# amc6821-breakout-v2_0.net
KiCad netlist of a schematic drawn in EAGLE
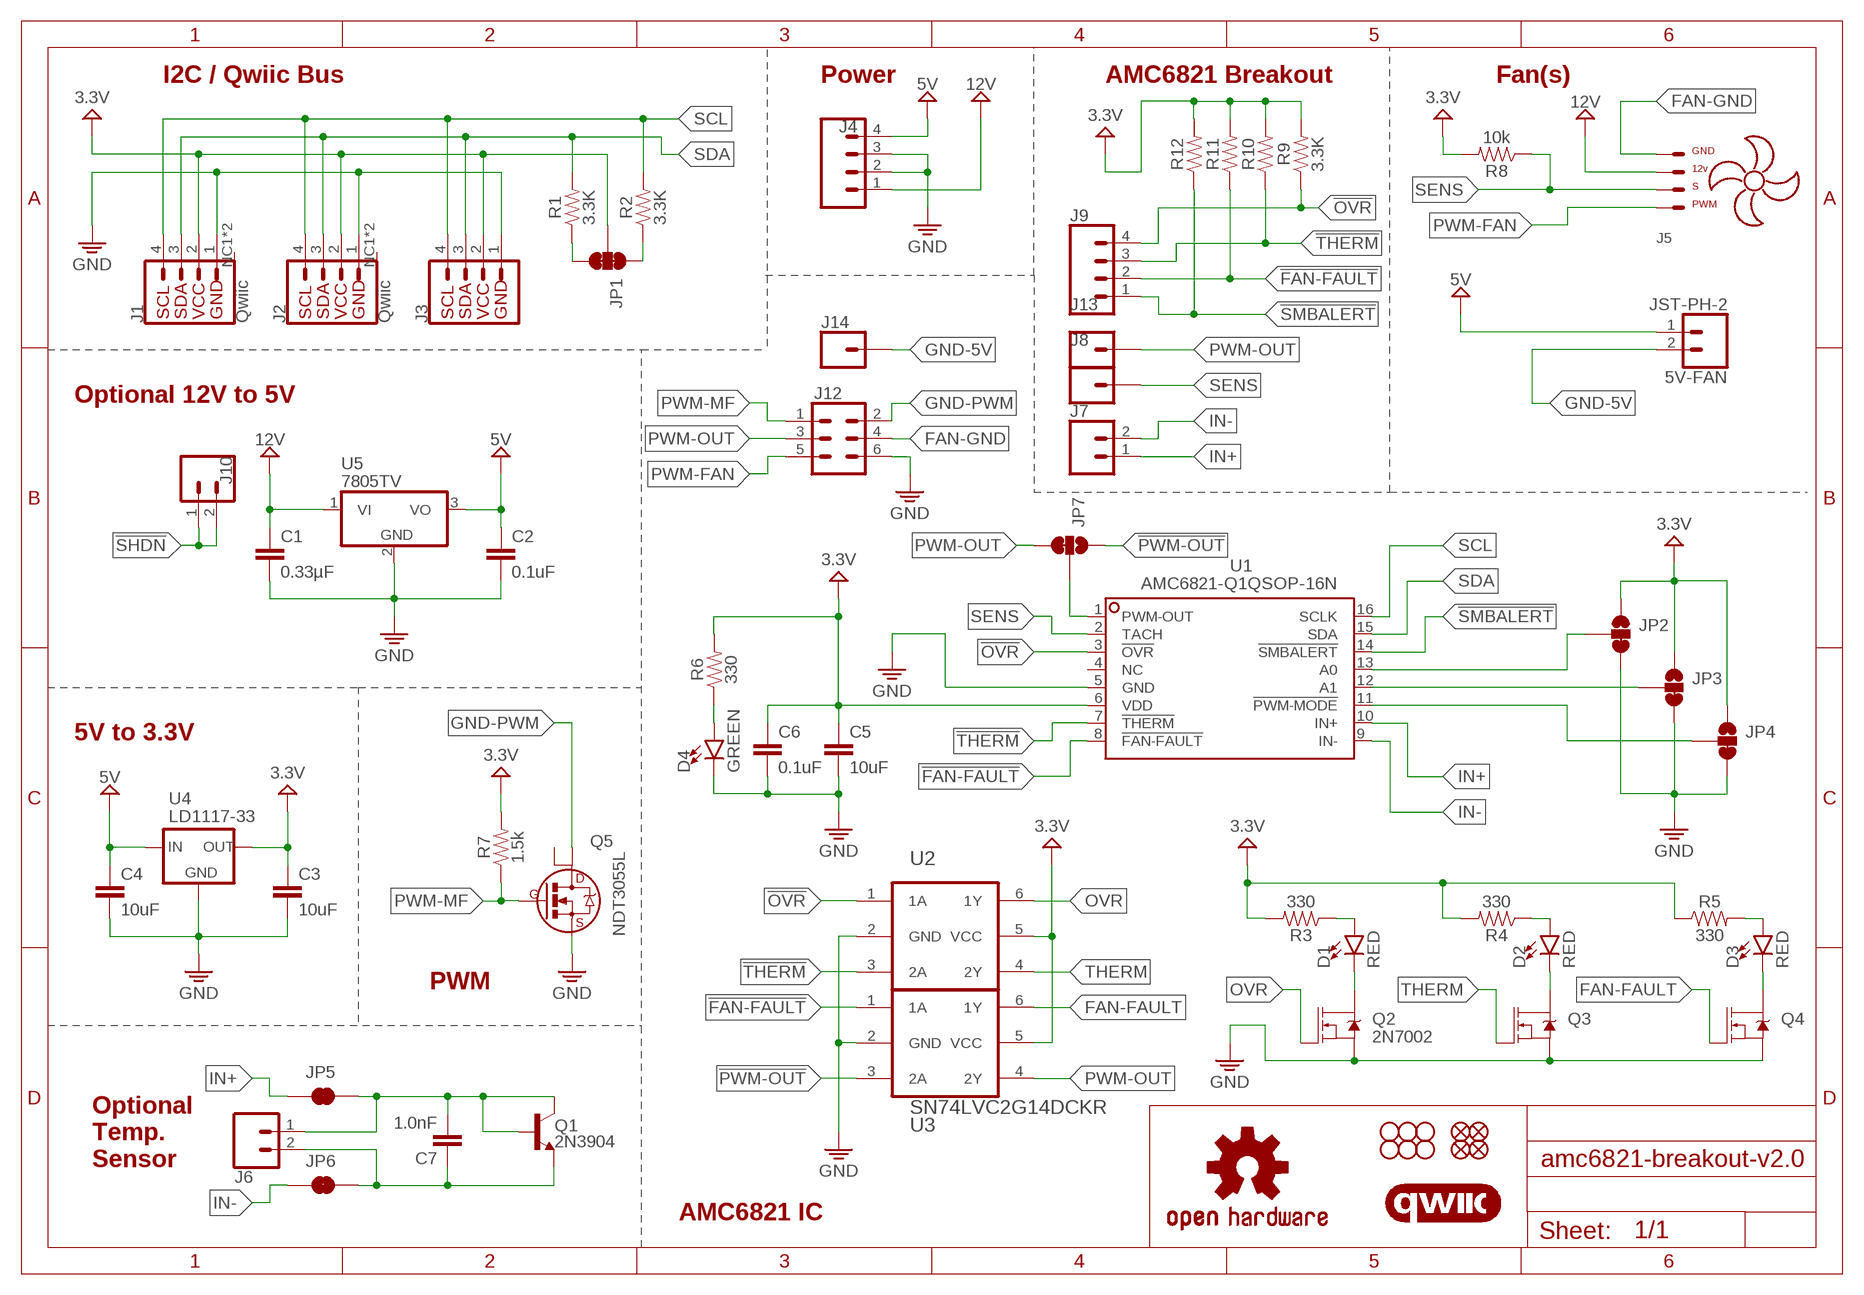
[diagram p0: schematic, sheet 1]

(export (version "E")
  (design (tool "Eeschema 10.0.6"))
  (components
    (comp (ref "5V-FAN")
      (value "JST-PH-2")
      (footprint "eagle-import:JST-PH2")
      (libsource (lib "eagle-import") (part "JST-PH-2"))
    )
    (comp (ref "C1")
      (value "0.33µF")
      (footprint "eagle-import:0805")
      (libsource (lib "eagle-import") (part "0.33UF/330NF-0805-50V-10%"))
    )
    (comp (ref "C2")
      (value "0.1uF")
      (footprint "eagle-import:0603")
      (libsource (lib "eagle-import") (part "0.1UF-0603-25V-5%"))
    )
    (comp (ref "C3")
      (value "10uF")
      (footprint "eagle-import:0603")
      (libsource (lib "eagle-import") (part "10UF-0603-6.3V-20%"))
    )
    (comp (ref "C4")
      (value "10uF")
      (footprint "eagle-import:0603")
      (libsource (lib "eagle-import") (part "10UF-0603-6.3V-20%"))
    )
    (comp (ref "C5")
      (value "10uF")
      (footprint "eagle-import:0603")
      (libsource (lib "eagle-import") (part "10UF-0603-6.3V-20%"))
    )
    (comp (ref "C6")
      (value "0.1uF")
      (footprint "eagle-import:0603")
      (libsource (lib "eagle-import") (part "0.1UF-0603-25V-5%"))
    )
    (comp (ref "C7")
      (value "1.0nF")
      (footprint "eagle-import:0402-TIGHT")
      (libsource (lib "eagle-import") (part "1.0NF/1000PF-0402_TIGHT-50V-10%"))
    )
    (comp (ref "D1")
      (value "RED")
      (footprint "eagle-import:LED-0603")
      (libsource (lib "eagle-import") (part "LED-RED0603"))
    )
    (comp (ref "D2")
      (value "RED")
      (footprint "eagle-import:LED-0603")
      (libsource (lib "eagle-import") (part "LED-RED0603"))
    )
    (comp (ref "D3")
      (value "RED")
      (footprint "eagle-import:LED-0603")
      (libsource (lib "eagle-import") (part "LED-RED0603"))
    )
    (comp (ref "D4")
      (value "GREEN")
      (footprint "eagle-import:LED-0603")
      (libsource (lib "eagle-import") (part "LED-GREEN0603"))
    )
    (comp (ref "FD1")
      (value "FIDUCIALUFIDUCIAL")
      (footprint "eagle-import:FIDUCIAL-MICRO")
      (libsource (lib "eagle-import") (part "FIDUCIALUFIDUCIAL"))
    )
    (comp (ref "FD2")
      (value "FIDUCIALUFIDUCIAL")
      (footprint "eagle-import:FIDUCIAL-MICRO")
      (libsource (lib "eagle-import") (part "FIDUCIALUFIDUCIAL"))
    )
    (comp (ref "FD3")
      (value "FIDUCIALUFIDUCIAL")
      (footprint "eagle-import:FIDUCIAL-MICRO")
      (libsource (lib "eagle-import") (part "FIDUCIALUFIDUCIAL"))
    )
    (comp (ref "FD4")
      (value "FIDUCIALUFIDUCIAL")
      (footprint "eagle-import:FIDUCIAL-MICRO")
      (libsource (lib "eagle-import") (part "FIDUCIALUFIDUCIAL"))
    )
    (comp (ref "H1")
      (value "STAND-OFF")
      (footprint "eagle-import:STAND-OFF")
      (libsource (lib "eagle-import") (part "STAND-OFF"))
    )
    (comp (ref "H2")
      (value "STAND-OFF")
      (footprint "eagle-import:STAND-OFF")
      (libsource (lib "eagle-import") (part "STAND-OFF"))
    )
    (comp (ref "H3")
      (value "STAND-OFF")
      (footprint "eagle-import:STAND-OFF")
      (libsource (lib "eagle-import") (part "STAND-OFF"))
    )
    (comp (ref "H4")
      (value "STAND-OFF")
      (footprint "eagle-import:STAND-OFF")
      (libsource (lib "eagle-import") (part "STAND-OFF"))
    )
    (comp (ref "H5")
      (value "STAND-OFF")
      (footprint "eagle-import:STAND-OFF")
      (libsource (lib "eagle-import") (part "STAND-OFF"))
    )
    (comp (ref "H6")
      (value "STAND-OFF")
      (footprint "eagle-import:STAND-OFF")
      (libsource (lib "eagle-import") (part "STAND-OFF"))
    )
    (comp (ref "J1")
      (value "Qwiic")
      (footprint "eagle-import:JST04_1MM_VERT")
      (libsource (lib "eagle-import") (part "QWIIC_CONNECTOR"))
    )
    (comp (ref "J2")
      (value "Qwiic")
      (footprint "eagle-import:JST04_1MM_VERT")
      (libsource (lib "eagle-import") (part "QWIIC_CONNECTOR"))
    )
    (comp (ref "J3")
      (value "I2C_STANDARD")
      (footprint "eagle-import:1X04")
      (libsource (lib "eagle-import") (part "I2C_STANDARD"))
    )
    (comp (ref "J4")
      (value "CONN_04SCREW")
      (footprint "eagle-import:SCREWTERMINAL-3.5MM-4")
      (libsource (lib "eagle-import") (part "CONN_04SCREW"))
    )
    (comp (ref "J5")
      (value "KK-254-4KK-254")
      (footprint "eagle-import:MOLEX_47053-1000")
      (libsource (lib "eagle-import") (part "KK-254-4KK-254"))
    )
    (comp (ref "J6")
      (value "CONN_02")
      (footprint "eagle-import:1X02")
      (libsource (lib "eagle-import") (part "CONN_02"))
    )
    (comp (ref "J7")
      (value "CONN_02")
      (footprint "eagle-import:1X02")
      (libsource (lib "eagle-import") (part "CONN_02"))
    )
    (comp (ref "J8")
      (value "CONN_01")
      (footprint "eagle-import:1X01")
      (libsource (lib "eagle-import") (part "CONN_01"))
    )
    (comp (ref "J9")
      (value "CONN_04PTH")
      (footprint "eagle-import:1X04")
      (libsource (lib "eagle-import") (part "CONN_04PTH"))
    )
    (comp (ref "J10")
      (value "CONN_021X02_NO_SILK")
      (footprint "eagle-import:1X02_NO_SILK")
      (libsource (lib "eagle-import") (part "CONN_021X02_NO_SILK"))
    )
    (comp (ref "J12")
      (value "CONN_03X2NO_SILK")
      (footprint "eagle-import:2X3-NS")
      (libsource (lib "eagle-import") (part "CONN_03X2NO_SILK"))
    )
    (comp (ref "J13")
      (value "CONN_01")
      (footprint "eagle-import:1X01")
      (libsource (lib "eagle-import") (part "CONN_01"))
    )
    (comp (ref "J14")
      (value "CONN_01")
      (footprint "eagle-import:1X01")
      (libsource (lib "eagle-import") (part "CONN_01"))
    )
    (comp (ref "JP1")
      (value "JUMPER-SMT_3_2-NC_TRACE_SILK")
      (footprint "eagle-import:SMT-JUMPER_3_2-NC_TRACE_SILK")
      (libsource (lib "eagle-import") (part "JUMPER-SMT_3_2-NC_TRACE_SILK"))
    )
    (comp (ref "JP2")
      (value "JUMPER-SMT_3_1-NC_TRACE_SILK")
      (footprint "eagle-import:SMT-JUMPER_3_1-NC_TRACE_SILK")
      (libsource (lib "eagle-import") (part "JUMPER-SMT_3_1-NC_TRACE_SILK"))
    )
    (comp (ref "JP3")
      (value "JUMPER-SMT_3_1-NC_TRACE_SILK")
      (footprint "eagle-import:SMT-JUMPER_3_1-NC_TRACE_SILK")
      (libsource (lib "eagle-import") (part "JUMPER-SMT_3_1-NC_TRACE_SILK"))
    )
    (comp (ref "JP4")
      (value "JUMPER-SMT_3_1-NC_TRACE_SILK")
      (footprint "eagle-import:SMT-JUMPER_3_1-NC_TRACE_SILK")
      (libsource (lib "eagle-import") (part "JUMPER-SMT_3_1-NC_TRACE_SILK"))
    )
    (comp (ref "JP5")
      (value "JUMPER-SMT_2_NC_TRACE_SILK")
      (footprint "eagle-import:SMT-JUMPER_2_NC_TRACE_SILK")
      (libsource (lib "eagle-import") (part "JUMPER-SMT_2_NC_TRACE_SILK"))
    )
    (comp (ref "JP6")
      (value "JUMPER-SMT_2_NC_TRACE_SILK")
      (footprint "eagle-import:SMT-JUMPER_2_NC_TRACE_SILK")
      (libsource (lib "eagle-import") (part "JUMPER-SMT_2_NC_TRACE_SILK"))
    )
    (comp (ref "JP7")
      (value "JUMPER-SMT_3_1-NC_TRACE_SILK")
      (footprint "eagle-import:SMT-JUMPER_3_1-NC_TRACE_SILK")
      (libsource (lib "eagle-import") (part "JUMPER-SMT_3_1-NC_TRACE_SILK"))
    )
    (comp (ref "LOGO1")
      (value "OSHW-LOGOS")
      (footprint "eagle-import:OSHW-LOGO-S")
      (libsource (lib "eagle-import") (part "OSHW-LOGOS"))
    )
    (comp (ref "LOGO2")
      (value "QWIIC_LOGO_6MM")
      (footprint "eagle-import:QWIIC_6MM")
      (libsource (lib "eagle-import") (part "QWIIC_LOGO_6MM"))
    )
    (comp (ref "Q1")
      (value "2N3904")
      (footprint "eagle-import:SOT23-3")
      (libsource (lib "eagle-import") (part "TRANS_NPN-MMBTA42"))
    )
    (comp (ref "Q2")
      (value "2N7002")
      (footprint "eagle-import:SOT323")
      (libsource (lib "eagle-import") (part "MOSFET-NCH-2N7002PW"))
    )
    (comp (ref "Q3")
      (value "310mA/60V/1.6Ω")
      (footprint "eagle-import:SOT323")
      (libsource (lib "eagle-import") (part "MOSFET-NCH-2N7002PW"))
    )
    (comp (ref "Q4")
      (value "310mA/60V/1.6Ω")
      (footprint "eagle-import:SOT323")
      (libsource (lib "eagle-import") (part "MOSFET-NCH-2N7002PW"))
    )
    (comp (ref "Q5")
      (value "NDT3055L")
      (footprint "eagle-import:SOT223")
      (libsource (lib "eagle-import") (part "NDT3055L"))
    )
    (comp (ref "R1")
      (value "3.3K")
      (footprint "eagle-import:0805")
      (libsource (lib "eagle-import") (part "RESISTOR0805"))
    )
    (comp (ref "R2")
      (value "3.3K")
      (footprint "eagle-import:0805")
      (libsource (lib "eagle-import") (part "RESISTOR0805"))
    )
    (comp (ref "R3")
      (value "330")
      (footprint "eagle-import:0805")
      (libsource (lib "eagle-import") (part "RESISTOR0805"))
    )
    (comp (ref "R4")
      (value "330")
      (footprint "eagle-import:0805")
      (libsource (lib "eagle-import") (part "RESISTOR0805"))
    )
    (comp (ref "R5")
      (value "330")
      (footprint "eagle-import:0805")
      (libsource (lib "eagle-import") (part "RESISTOR0805"))
    )
    (comp (ref "R6")
      (value "330")
      (footprint "eagle-import:0805")
      (libsource (lib "eagle-import") (part "RESISTOR0805"))
    )
    (comp (ref "R7")
      (value "1.5k")
      (footprint "eagle-import:0603")
      (libsource (lib "eagle-import") (part "1.5KOHM-0603-1/10W-1%"))
    )
    (comp (ref "R8")
      (value "10k")
      (footprint "eagle-import:0603")
      (libsource (lib "eagle-import") (part "10KOHM-0603-1/10W-1%"))
    )
    (comp (ref "R9")
      (value "3.3K")
      (footprint "eagle-import:0805")
      (libsource (lib "eagle-import") (part "RESISTOR0805"))
    )
    (comp (ref "R10")
      (value "3.3K")
      (footprint "eagle-import:0805")
      (libsource (lib "eagle-import") (part "RESISTOR0805"))
    )
    (comp (ref "R11")
      (value "3.3K")
      (footprint "eagle-import:0805")
      (libsource (lib "eagle-import") (part "RESISTOR0805"))
    )
    (comp (ref "R12")
      (value "3.3K")
      (footprint "eagle-import:0805")
      (libsource (lib "eagle-import") (part "RESISTOR0805"))
    )
    (comp (ref "U1")
      (value "AMC6821-Q1QSOP-16N")
      (footprint "eagle-import:QSOP-16N")
      (libsource (lib "eagle-import") (part "AMC6821-Q1QSOP-16N"))
    )
    (comp (ref "U2")
      (value "SN74LVC2G14DCKR")
      (footprint "eagle-import:SOT65P210X110-6N")
      (libsource (lib "eagle-import") (part "SN74LVC2G14DCKR"))
    )
    (comp (ref "U3")
      (value "SN74LVC2G14DCKR")
      (footprint "eagle-import:SOT65P210X110-6N")
      (libsource (lib "eagle-import") (part "SN74LVC2G14DCKR"))
    )
    (comp (ref "U4")
      (value "LD1117-33")
      (footprint "eagle-import:SOT223")
      (libsource (lib "eagle-import") (part "V_REG_LD1117VXXLD1117-SMD"))
    )
    (comp (ref "U5")
      (value "7805TV")
      (footprint "eagle-import:TO220V")
      (libsource (lib "eagle-import") (part "78TV05"))
    )
  )
  (nets
    (net (code "1") (name "/~{FAN-FAULT}") (class "Default")
      (node (ref "J9") (pin "2") (pinfunction "2_2") (pintype "passive"))
      (node (ref "R11") (pin "1") (pinfunction "1_1") (pintype "passive"))
      (node (ref "U1") (pin "8") (pinfunction "~{FAN-FAULT}_8") (pintype "output"))
      (node (ref "U3") (pin "1") (pinfunction "1A_1") (pintype "input"))
    )
    (net (code "2") (name "/~{OVR}") (class "Default")
      (node (ref "J9") (pin "4") (pinfunction "4_4") (pintype "passive"))
      (node (ref "R9") (pin "1") (pinfunction "1_1") (pintype "passive"))
      (node (ref "U1") (pin "3") (pinfunction "~{OVR}_3") (pintype "output"))
      (node (ref "U2") (pin "1") (pinfunction "1A_1") (pintype "input"))
    )
    (net (code "3") (name "/~{PWM-OUT}") (class "Default")
      (node (ref "JP7") (pin "1") (pinfunction "1_1") (pintype "passive"))
      (node (ref "U3") (pin "3") (pinfunction "2A_3") (pintype "input"))
    )
    (net (code "4") (name "/~{SHDN}") (class "Default")
      (node (ref "J10") (pin "1") (pinfunction "1_1") (pintype "passive"))
      (node (ref "J10") (pin "2") (pinfunction "2_2") (pintype "passive"))
    )
    (net (code "5") (name "/~{SMBALERT}") (class "Default")
      (node (ref "J9") (pin "1") (pinfunction "1_1") (pintype "passive"))
      (node (ref "R12") (pin "1") (pinfunction "1_1") (pintype "passive"))
      (node (ref "U1") (pin "14") (pinfunction "~{SMBALERT}_14") (pintype "input"))
    )
    (net (code "6") (name "/~{THERM}") (class "Default")
      (node (ref "J9") (pin "3") (pinfunction "3_3") (pintype "passive"))
      (node (ref "R10") (pin "1") (pinfunction "1_1") (pintype "passive"))
      (node (ref "U1") (pin "7") (pinfunction "~{THERM}_7") (pintype "bidirectional"))
      (node (ref "U2") (pin "3") (pinfunction "2A_3") (pintype "input"))
    )
    (net (code "7") (name "3.3V") (class "Default")
      (node (ref "C3") (pin "1") (pinfunction "1_1") (pintype "passive"))
      (node (ref "C5") (pin "1") (pinfunction "1_1") (pintype "passive"))
      (node (ref "C6") (pin "1") (pinfunction "1_1") (pintype "passive"))
      (node (ref "J1") (pin "2") (pinfunction "2_2") (pintype "power_in"))
      (node (ref "J2") (pin "2") (pinfunction "2_2") (pintype "power_in"))
      (node (ref "J3") (pin "2") (pinfunction "2_2") (pintype "power_in"))
      (node (ref "JP1") (pin "2") (pinfunction "2_2") (pintype "passive"))
      (node (ref "JP2") (pin "1") (pinfunction "1_1") (pintype "passive"))
      (node (ref "JP3") (pin "1") (pinfunction "1_1") (pintype "passive"))
      (node (ref "JP4") (pin "1") (pinfunction "1_1") (pintype "passive"))
      (node (ref "R10") (pin "2") (pinfunction "2_2") (pintype "passive"))
      (node (ref "R11") (pin "2") (pinfunction "2_2") (pintype "passive"))
      (node (ref "R12") (pin "2") (pinfunction "2_2") (pintype "passive"))
      (node (ref "R3") (pin "2") (pinfunction "2_2") (pintype "passive"))
      (node (ref "R4") (pin "2") (pinfunction "2_2") (pintype "passive"))
      (node (ref "R5") (pin "1") (pinfunction "1_1") (pintype "passive"))
      (node (ref "R6") (pin "2") (pinfunction "2_2") (pintype "passive"))
      (node (ref "R7") (pin "2") (pinfunction "2_2") (pintype "passive"))
      (node (ref "R8") (pin "2") (pinfunction "2_2") (pintype "passive"))
      (node (ref "R9") (pin "2") (pinfunction "2_2") (pintype "passive"))
      (node (ref "U1") (pin "6") (pinfunction "VDD_6") (pintype "power_in"))
      (node (ref "U2") (pin "5") (pinfunction "VCC_5") (pintype "power_in"))
      (node (ref "U3") (pin "5") (pinfunction "VCC_5") (pintype "power_in"))
      (node (ref "U4") (pin "2") (pinfunction "OUT_2") (pintype "passive"))
    )
    (net (code "8") (name "5V") (class "Default")
      (node (ref "5V-FAN") (pin "1") (pinfunction "1_1") (pintype "passive"))
      (node (ref "C2") (pin "1") (pinfunction "1_1") (pintype "passive"))
      (node (ref "C4") (pin "1") (pinfunction "1_1") (pintype "passive"))
      (node (ref "J4") (pin "4") (pinfunction "4_4") (pintype "passive"))
      (node (ref "U4") (pin "3") (pinfunction "IN_3") (pintype "input"))
      (node (ref "U5") (pin "3") (pinfunction "VO_3") (pintype "passive"))
    )
    (net (code "9") (name "12V") (class "Default")
      (node (ref "C1") (pin "1") (pinfunction "1_1") (pintype "passive"))
      (node (ref "J4") (pin "1") (pinfunction "1_1") (pintype "passive"))
      (node (ref "J5") (pin "2:+12VDC") (pinfunction "2:+12VDC_2:+12VDC") (pintype "power_in"))
      (node (ref "U5") (pin "1") (pinfunction "VI_1") (pintype "input"))
    )
    (net (code "10") (name "FAN-FAULT") (class "Default")
      (node (ref "Q4") (pin "1") (pinfunction "G_1") (pintype "bidirectional"))
      (node (ref "U3") (pin "6") (pinfunction "1Y_6") (pintype "output"))
    )
    (net (code "11") (name "FAN-GND") (class "Default")
      (node (ref "J12") (pin "4") (pinfunction "4_4") (pintype "bidirectional"))
      (node (ref "J5") (pin "1:GND") (pinfunction "1:GND_1:GND") (pintype "power_in"))
    )
    (net (code "12") (name "GND") (class "Default")
      (node (ref "C1") (pin "2") (pinfunction "2_2") (pintype "passive"))
      (node (ref "C2") (pin "2") (pinfunction "2_2") (pintype "passive"))
      (node (ref "C3") (pin "2") (pinfunction "2_2") (pintype "passive"))
      (node (ref "C4") (pin "2") (pinfunction "2_2") (pintype "passive"))
      (node (ref "C5") (pin "2") (pinfunction "2_2") (pintype "passive"))
      (node (ref "C6") (pin "2") (pinfunction "2_2") (pintype "passive"))
      (node (ref "D4") (pin "C") (pinfunction "C_C") (pintype "passive"))
      (node (ref "J1") (pin "1") (pinfunction "1_1") (pintype "power_in"))
      (node (ref "J12") (pin "6") (pinfunction "6_6") (pintype "bidirectional"))
      (node (ref "J2") (pin "1") (pinfunction "1_1") (pintype "power_in"))
      (node (ref "J3") (pin "1") (pinfunction "1_1") (pintype "power_in"))
      (node (ref "J4") (pin "2") (pinfunction "2_2") (pintype "passive"))
      (node (ref "J4") (pin "3") (pinfunction "3_3") (pintype "passive"))
      (node (ref "JP2") (pin "3") (pinfunction "3_3") (pintype "passive"))
      (node (ref "JP3") (pin "3") (pinfunction "3_3") (pintype "passive"))
      (node (ref "JP4") (pin "3") (pinfunction "3_3") (pintype "passive"))
      (node (ref "Q2") (pin "2") (pinfunction "S_2") (pintype "bidirectional"))
      (node (ref "Q3") (pin "2") (pinfunction "S_2") (pintype "bidirectional"))
      (node (ref "Q4") (pin "2") (pinfunction "S_2") (pintype "bidirectional"))
      (node (ref "Q5") (pin "S") (pinfunction "S_S") (pintype "passive"))
      (node (ref "U1") (pin "5") (pinfunction "GND_5") (pintype "power_in"))
      (node (ref "U2") (pin "2") (pinfunction "GND_2") (pintype "passive"))
      (node (ref "U3") (pin "2") (pinfunction "GND_2") (pintype "passive"))
      (node (ref "U4") (pin "1") (pinfunction "GND_1") (pintype "input"))
      (node (ref "U5") (pin "2") (pinfunction "GND_2") (pintype "passive"))
    )
    (net (code "13") (name "GND-5V") (class "Default")
      (node (ref "5V-FAN") (pin "2") (pinfunction "2_2") (pintype "passive"))
      (node (ref "J14") (pin "1") (pinfunction "1_1") (pintype "passive"))
    )
    (net (code "14") (name "GND-PWM") (class "Default")
      (node (ref "J12") (pin "2") (pinfunction "2_2") (pintype "bidirectional"))
      (node (ref "Q5") (pin "D") (pinfunction "D_D") (pintype "passive"))
    )
    (net (code "15") (name "IN+") (class "Default")
      (node (ref "J7") (pin "1") (pinfunction "1_1") (pintype "passive"))
      (node (ref "JP5") (pin "1") (pinfunction "1_1") (pintype "passive"))
      (node (ref "U1") (pin "10") (pinfunction "IN+_10") (pintype "output"))
    )
    (net (code "16") (name "IN-") (class "Default")
      (node (ref "J7") (pin "2") (pinfunction "2_2") (pintype "passive"))
      (node (ref "JP6") (pin "1") (pinfunction "1_1") (pintype "passive"))
      (node (ref "U1") (pin "9") (pinfunction "IN-_9") (pintype "input"))
    )
    (net (code "17") (name "Net-(D1-PadA)") (class "Default")
      (node (ref "D1") (pin "A") (pinfunction "A_A") (pintype "passive"))
      (node (ref "R3") (pin "1") (pinfunction "1_1") (pintype "passive"))
    )
    (net (code "18") (name "Net-(D2-PadA)") (class "Default")
      (node (ref "D2") (pin "A") (pinfunction "A_A") (pintype "passive"))
      (node (ref "R4") (pin "1") (pinfunction "1_1") (pintype "passive"))
    )
    (net (code "19") (name "Net-(D3-PadA)") (class "Default")
      (node (ref "D3") (pin "A") (pinfunction "A_A") (pintype "passive"))
      (node (ref "R5") (pin "2") (pinfunction "2_2") (pintype "passive"))
    )
    (net (code "20") (name "Net-(D4-PadA)") (class "Default")
      (node (ref "D4") (pin "A") (pinfunction "A_A") (pintype "passive"))
      (node (ref "R6") (pin "1") (pinfunction "1_1") (pintype "passive"))
    )
    (net (code "21") (name "Net-(JP1-Pad1)") (class "Default")
      (node (ref "JP1") (pin "1") (pinfunction "1_1") (pintype "passive"))
      (node (ref "R2") (pin "1") (pinfunction "1_1") (pintype "passive"))
    )
    (net (code "22") (name "Net-(JP1-Pad3)") (class "Default")
      (node (ref "JP1") (pin "3") (pinfunction "3_3") (pintype "passive"))
      (node (ref "R1") (pin "1") (pinfunction "1_1") (pintype "passive"))
    )
    (net (code "23") (name "Net-(Q1-B)") (class "Default")
      (node (ref "C7") (pin "2") (pinfunction "2_2") (pintype "passive"))
      (node (ref "J6") (pin "1") (pinfunction "1_1") (pintype "passive"))
      (node (ref "JP5") (pin "2") (pinfunction "2_2") (pintype "passive"))
      (node (ref "Q1") (pin "1") (pinfunction "B_1") (pintype "passive"))
      (node (ref "Q1") (pin "3") (pinfunction "C_3") (pintype "passive"))
    )
    (net (code "24") (name "Net-(Q1-E)") (class "Default")
      (node (ref "C7") (pin "1") (pinfunction "1_1") (pintype "passive"))
      (node (ref "J6") (pin "2") (pinfunction "2_2") (pintype "passive"))
      (node (ref "JP6") (pin "2") (pinfunction "2_2") (pintype "passive"))
      (node (ref "Q1") (pin "2") (pinfunction "E_2") (pintype "passive"))
    )
    (net (code "25") (name "Net-(Q2-D)") (class "Default")
      (node (ref "D1") (pin "C") (pinfunction "C_C") (pintype "passive"))
      (node (ref "Q2") (pin "3") (pinfunction "D_3") (pintype "bidirectional"))
    )
    (net (code "26") (name "Net-(Q3-D)") (class "Default")
      (node (ref "D2") (pin "C") (pinfunction "C_C") (pintype "passive"))
      (node (ref "Q3") (pin "3") (pinfunction "D_3") (pintype "bidirectional"))
    )
    (net (code "27") (name "Net-(Q4-D)") (class "Default")
      (node (ref "D3") (pin "C") (pinfunction "C_C") (pintype "passive"))
      (node (ref "Q4") (pin "3") (pinfunction "D_3") (pintype "bidirectional"))
    )
    (net (code "28") (name "Net-(U1-A0)") (class "Default")
      (node (ref "JP2") (pin "2") (pinfunction "2_2") (pintype "passive"))
      (node (ref "U1") (pin "13") (pinfunction "A0_13") (pintype "input"))
    )
    (net (code "29") (name "Net-(U1-A1)") (class "Default")
      (node (ref "JP3") (pin "2") (pinfunction "2_2") (pintype "passive"))
      (node (ref "U1") (pin "12") (pinfunction "A1_12") (pintype "input"))
    )
    (net (code "30") (name "Net-(U1-PWM-OUT)") (class "Default")
      (node (ref "JP7") (pin "2") (pinfunction "2_2") (pintype "passive"))
      (node (ref "U1") (pin "1") (pinfunction "PWM-OUT_1") (pintype "output"))
    )
    (net (code "31") (name "Net-(U1-~{PWM-MODE})") (class "Default")
      (node (ref "JP4") (pin "2") (pinfunction "2_2") (pintype "passive"))
      (node (ref "U1") (pin "11") (pinfunction "~{PWM-MODE}_11") (pintype "input"))
    )
    (net (code "32") (name "OVR") (class "Default")
      (node (ref "Q2") (pin "1") (pinfunction "G_1") (pintype "bidirectional"))
      (node (ref "U2") (pin "6") (pinfunction "1Y_6") (pintype "output"))
    )
    (net (code "33") (name "PWM-FAN") (class "Default")
      (node (ref "J12") (pin "5") (pinfunction "5_5") (pintype "bidirectional"))
      (node (ref "J5") (pin "4:PWM") (pinfunction "4:PWM_4:PWM") (pintype "output"))
    )
    (net (code "34") (name "PWM-MF") (class "Default")
      (node (ref "J12") (pin "1") (pinfunction "1_1") (pintype "bidirectional"))
      (node (ref "Q5") (pin "G") (pinfunction "G_G") (pintype "passive"))
      (node (ref "R7") (pin "1") (pinfunction "1_1") (pintype "passive"))
    )
    (net (code "35") (name "PWM-OUT") (class "Default")
      (node (ref "J12") (pin "3") (pinfunction "3_3") (pintype "bidirectional"))
      (node (ref "J13") (pin "1") (pinfunction "1_1") (pintype "passive"))
      (node (ref "JP7") (pin "3") (pinfunction "3_3") (pintype "passive"))
      (node (ref "U3") (pin "4") (pinfunction "2Y_4") (pintype "output"))
    )
    (net (code "36") (name "SCL") (class "Default")
      (node (ref "J1") (pin "4") (pinfunction "4_4") (pintype "passive"))
      (node (ref "J2") (pin "4") (pinfunction "4_4") (pintype "passive"))
      (node (ref "J3") (pin "4") (pinfunction "4_4") (pintype "passive"))
      (node (ref "R2") (pin "2") (pinfunction "2_2") (pintype "passive"))
      (node (ref "U1") (pin "16") (pinfunction "SCLK_16") (pintype "input"))
    )
    (net (code "37") (name "SDA") (class "Default")
      (node (ref "J1") (pin "3") (pinfunction "3_3") (pintype "passive"))
      (node (ref "J2") (pin "3") (pinfunction "3_3") (pintype "passive"))
      (node (ref "J3") (pin "3") (pinfunction "3_3") (pintype "passive"))
      (node (ref "R1") (pin "2") (pinfunction "2_2") (pintype "passive"))
      (node (ref "U1") (pin "15") (pinfunction "SDA_15") (pintype "bidirectional"))
    )
    (net (code "38") (name "SENS") (class "Default")
      (node (ref "J5") (pin "3:TACH") (pinfunction "3:TACH_3:TACH") (pintype "input"))
      (node (ref "J8") (pin "1") (pinfunction "1_1") (pintype "passive"))
      (node (ref "R8") (pin "1") (pinfunction "1_1") (pintype "passive"))
      (node (ref "U1") (pin "2") (pinfunction "TACH_2") (pintype "input"))
    )
    (net (code "39") (name "THERM") (class "Default")
      (node (ref "Q3") (pin "1") (pinfunction "G_1") (pintype "bidirectional"))
      (node (ref "U2") (pin "4") (pinfunction "2Y_4") (pintype "output"))
    )
    (net (code "40") (name "unconnected-(J1-SH-PadNC1)") (class "Default")
      (node (ref "J1") (pin "NC1") (pinfunction "SH_NC1") (pintype "no_connect"))
    )
    (net (code "41") (name "unconnected-(J1-SH-PadNC2)") (class "Default")
      (node (ref "J1") (pin "NC2") (pinfunction "SH_NC2") (pintype "no_connect"))
    )
    (net (code "42") (name "unconnected-(J2-SH-PadNC1)") (class "Default")
      (node (ref "J2") (pin "NC1") (pinfunction "SH_NC1") (pintype "no_connect"))
    )
    (net (code "43") (name "unconnected-(J2-SH-PadNC2)") (class "Default")
      (node (ref "J2") (pin "NC2") (pinfunction "SH_NC2") (pintype "no_connect"))
    )
    (net (code "44") (name "unconnected-(Q5-PadD2)") (class "Default")
      (node (ref "Q5") (pin "D2") (pinfunction "D2_D2") (pintype "passive"))
    )
    (net (code "45") (name "unconnected-(U1-NC-Pad4)") (class "Default")
      (node (ref "U1") (pin "4") (pinfunction "NC_4") (pintype "no_connect"))
    )
  )
)
